# PowerSheet.net
KiCad netlist of a schematic drawn in Altium Designer
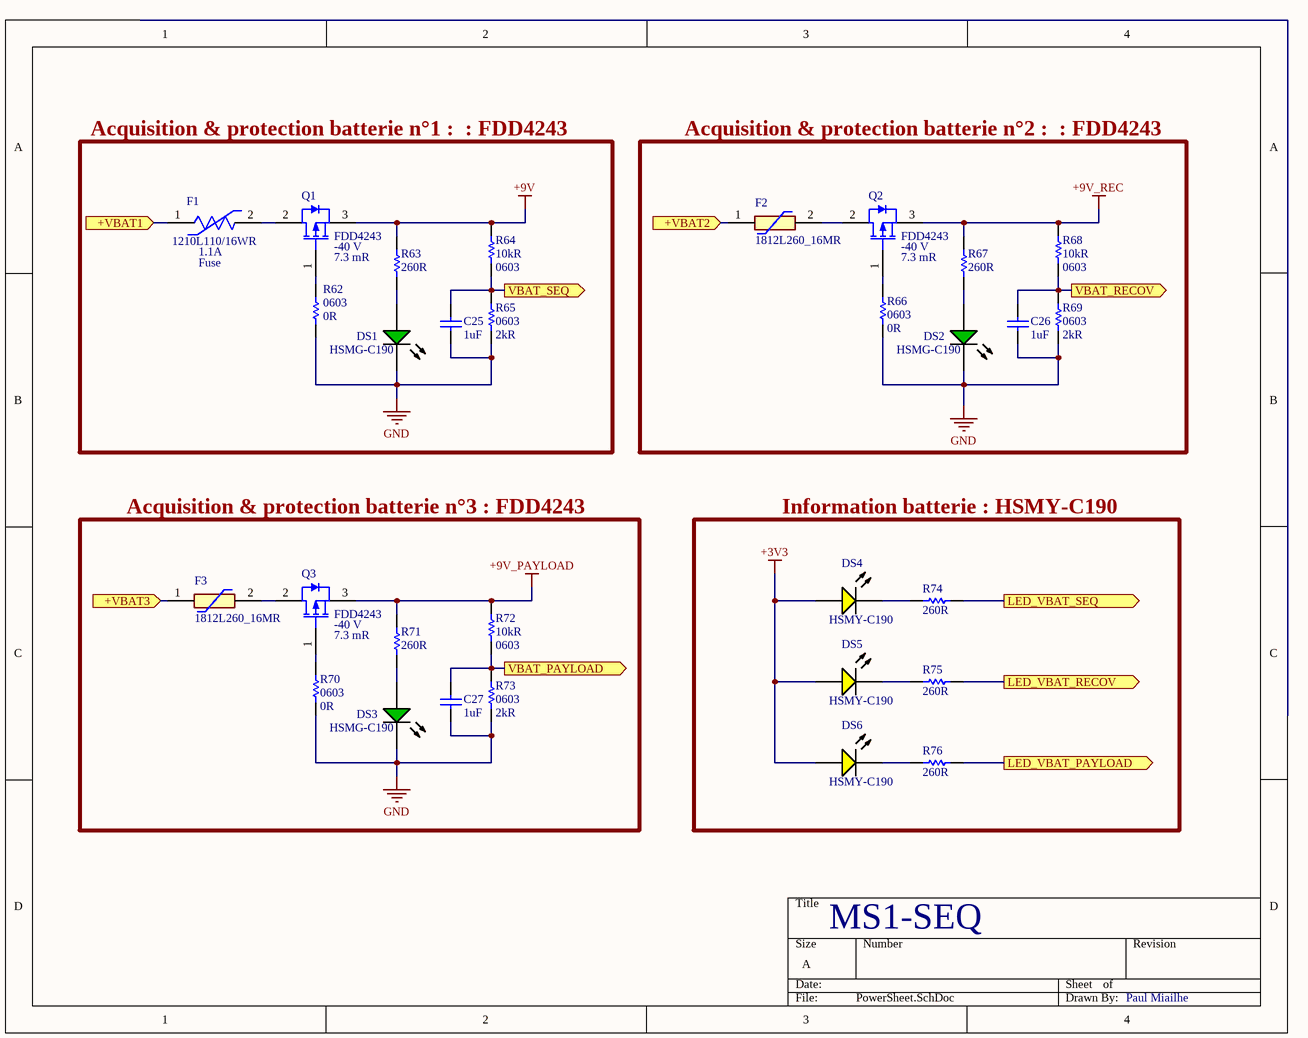
[diagram p0: PowerSheet.SchDoc]

(export (version "E")
  (design (tool "Eeschema 10.0.6"))
  (components
    (comp (ref "C25")
      (value "GRM188R61E105KA12D")
      (footprint "CAPC1608X90X35LL10T15")
      (fields
        (field (name "MANUFACTURER") "Murata")
        (field (name "CAPACITANCE") "1uF")
        (field (name "TOLERANCE") "10%")
        (field (name "VOLTAGE") "25V")
      )
      (libsource (lib "Altium Content Vault") (part "CAP"))
    )
    (comp (ref "C26")
      (value "GRM188R61E105KA12D")
      (footprint "CAPC1608X90X35LL10T15")
      (fields
        (field (name "MANUFACTURER") "Murata")
        (field (name "CAPACITANCE") "1uF")
        (field (name "TOLERANCE") "10%")
        (field (name "VOLTAGE") "25V")
      )
      (libsource (lib "Altium Content Vault") (part "CAP"))
    )
    (comp (ref "C27")
      (value "GRM188R61E105KA12D")
      (footprint "CAPC1608X90X35LL10T15")
      (fields
        (field (name "MANUFACTURER") "Murata")
        (field (name "CAPACITANCE") "1uF")
        (field (name "TOLERANCE") "10%")
        (field (name "VOLTAGE") "25V")
      )
      (libsource (lib "Altium Content Vault") (part "CAP"))
    )
    (comp (ref "DS1")
      (value "HSMG-C190")
      (footprint "AVAG-HSMX-C190_V")
      (description "Chip LED, Green, 2.2 V, -40 to 85 degC, 2-Pin SMD, RoHS, Tape and Reel")
      (libsource (lib "Altium Content Vault") (part "LED-GREEN-AK-2"))
    )
    (comp (ref "DS2")
      (value "HSMG-C190")
      (footprint "AVAG-HSMX-C190_V")
      (description "Chip LED, Green, 2.2 V, -40 to 85 degC, 2-Pin SMD, RoHS, Tape and Reel")
      (libsource (lib "Altium Content Vault") (part "LED-GREEN-AK-2"))
    )
    (comp (ref "DS3")
      (value "HSMG-C190")
      (footprint "AVAG-HSMX-C190_V")
      (description "Chip LED, Green, 2.2 V, -40 to 85 degC, 2-Pin SMD, RoHS, Tape and Reel")
      (libsource (lib "Altium Content Vault") (part "LED-GREEN-AK-2"))
    )
    (comp (ref "DS4")
      (value "HSMY-C190")
      (footprint "AVAG-HSMX-C190_V")
      (description "LED Uni-Color Yellow, 65 mW, 20 mA, -40 to 85 degC, 2-Pin SMD, RoHS, Tape and Reel")
      (fields (field (name "TOLERANCE") "1%"))
      (libsource (lib "Altium Content Vault") (part "LED-YELLOW-AK-2"))
    )
    (comp (ref "DS5")
      (value "HSMY-C190")
      (footprint "AVAG-HSMX-C190_V")
      (description "LED Uni-Color Yellow, 65 mW, 20 mA, -40 to 85 degC, 2-Pin SMD, RoHS, Tape and Reel")
      (fields (field (name "TOLERANCE") "1%"))
      (libsource (lib "Altium Content Vault") (part "LED-YELLOW-AK-2"))
    )
    (comp (ref "DS6")
      (value "HSMY-C190")
      (footprint "AVAG-HSMX-C190_V")
      (description "LED Uni-Color Yellow, 65 mW, 20 mA, -40 to 85 degC, 2-Pin SMD, RoHS, Tape and Reel")
      (fields (field (name "TOLERANCE") "1%"))
      (libsource (lib "Altium Content Vault") (part "LED-YELLOW-AK-2"))
    )
    (comp (ref "F1")
      (value "1210L110/16WR")
      (footprint "FP-1210L110-16WR-MFG")
      (description "PTC RESET FUSE 16V 1.1A 1210")
      (fields
        (field (name "HOLD CURRENT") "1.1A")
        (field (name "CATEGORY") "Fuse")
        (field (name "OCTOPART") "https://octopart.com/1210l110%2F16wr-littelfuse-28867107")
        (field (name "MANUFACTURER") "Littelfuse Inc")
      )
      (libsource (lib "Altium Content Vault") (part "1c6d77a0208143737455a0c7eb396be"))
    )
    (comp (ref "F2")
      (value "1812L260_16MR")
      (footprint "SamacSys:1812L010DR")
      (description "Resettable Fuse")
      (fields
        (field (name "MANUFACTURER_PART_NUMBER") "1812L260/16MR")
        (field (name "MOUSER PART NUMBER") "576-1812L260/16MR")
      )
      (libsource (lib "*") (part "1812L260_16MR"))
    )
    (comp (ref "F3")
      (value "1812L260_16MR")
      (footprint "SamacSys:1812L010DR")
      (description "Resettable Fuse")
      (fields
        (field (name "MANUFACTURER_PART_NUMBER") "1812L260/16MR")
        (field (name "MOUSER PART NUMBER") "576-1812L260/16MR")
      )
      (libsource (lib "*") (part "1812L260_16MR"))
    )
    (comp (ref "Q1")
      (value "FDD4243")
      (footprint "INF-PG-TO252-3-313_L")
      (description "OptiMOS-P2 Power-Transistor, -40 V VDS, -85 A ID, PG-TO252-3-313, Reel, Green")
      (fields
        (field (name "PARTNUMBER") "IPD85P04P4-07")
        (field (name "VDS (MAX)") "-40 V")
        (field (name "RDS (ON) (MAX) (@10V)") "7.3 mR")
        (field (name "MANUFACTURER") "Infineon")
      )
      (libsource (lib "Altium Content Vault") (part "INF-MOSFET-P-3"))
    )
    (comp (ref "Q2")
      (value "FDD4243")
      (footprint "INF-PG-TO252-3-313_L")
      (description "OptiMOS-P2 Power-Transistor, -40 V VDS, -85 A ID, PG-TO252-3-313, Reel, Green")
      (fields
        (field (name "PARTNUMBER") "IPD85P04P4-07")
        (field (name "VDS (MAX)") "-40 V")
        (field (name "RDS (ON) (MAX) (@10V)") "7.3 mR")
        (field (name "MANUFACTURER") "Infineon")
      )
      (libsource (lib "Altium Content Vault") (part "INF-MOSFET-P-3"))
    )
    (comp (ref "Q3")
      (value "FDD4243")
      (footprint "INF-PG-TO252-3-313_L")
      (description "OptiMOS-P2 Power-Transistor, -40 V VDS, -85 A ID, PG-TO252-3-313, Reel, Green")
      (fields
        (field (name "PARTNUMBER") "IPD85P04P4-07")
        (field (name "VDS (MAX)") "-40 V")
        (field (name "RDS (ON) (MAX) (@10V)") "7.3 mR")
        (field (name "MANUFACTURER") "Infineon")
      )
      (libsource (lib "Altium Content Vault") (part "INF-MOSFET-P-3"))
    )
    (comp (ref "R62")
      (value "RC0603JR-070RL")
      (footprint "RESC1608X55X25ML10T15")
      (description "Chip Resistor, 0 Ohm, +/- 5%, 0.1 W, -55 to 155 degC, 0603 (1608 Metric), RoHS, Tape and Reel")
      (fields
        (field (name "TOLERANCE") "5%")
        (field (name "PACKAGE REFERENCE") "0603")
        (field (name "RESISTANCE") "0R")
        (field (name "MANUFACTURER") "Yageo")
      )
      (libsource (lib "Altium Content Vault") (part "RES-2"))
    )
    (comp (ref "R63")
      (value "260R")
      (footprint "RESC1609X50X30NL8T20")
      (fields (field (name "MANUFACTURER") "Vishay Semiconductor"))
      (libsource (lib "Altium Content Vault") (part "RES-2"))
    )
    (comp (ref "R64")
      (value "ERJ3EKF1002V")
      (footprint "RESC1609X55X30LL15T15")
      (description "Chip Resistor, 10 KOhm, +/- 1%, 0.1 W, -55 to 155 degC, 0603 (1608 Metric), RoHS, Tape and Reel")
      (fields
        (field (name "RESISTANCE") "10kR")
        (field (name "CASE CODE (IMPERIAL)") "0603")
        (field (name "TOLERANCE") "1%")
        (field (name "MANUFACTURER") "Panasonic")
      )
      (libsource (lib "Altium Content Vault") (part "RES-2"))
    )
    (comp (ref "R65")
      (value "ERJ-3EKF2001V")
      (footprint "RESC1608X55X30ML15T15")
      (fields
        (field (name "MANUFACTURER") "Panasonic")
        (field (name "CASE CODE (IMPERIAL)") "0603")
        (field (name "RESISTANCE") "2kR")
        (field (name "TOLERANCE") "1%")
      )
      (libsource (lib "Altium Content Vault") (part "RES"))
    )
    (comp (ref "R66")
      (value "RC0603JR-070RL")
      (footprint "RESC1608X55X25ML10T15")
      (description "Chip Resistor, 0 Ohm, +/- 5%, 0.1 W, -55 to 155 degC, 0603 (1608 Metric), RoHS, Tape and Reel")
      (fields
        (field (name "TOLERANCE") "5%")
        (field (name "CASE CODE (IMPERIAL)") "0603")
        (field (name "RESISTANCE") "0R")
        (field (name "MANUFACTURER") "Yageo")
      )
      (libsource (lib "Altium Content Vault") (part "RES-2"))
    )
    (comp (ref "R67")
      (value "260R")
      (footprint "RESC1609X50X30NL8T20")
      (fields (field (name "MANUFACTURER") "Vishay Semiconductor"))
      (libsource (lib "Altium Content Vault") (part "RES-2"))
    )
    (comp (ref "R68")
      (value "ERJ3EKF1002V")
      (footprint "RESC1609X55X30LL15T15")
      (description "Chip Resistor, 10 KOhm, +/- 1%, 0.1 W, -55 to 155 degC, 0603 (1608 Metric), RoHS, Tape and Reel")
      (fields
        (field (name "RESISTANCE") "10kR")
        (field (name "CASE CODE (IMPERIAL)") "0603")
        (field (name "TOLERANCE") "1%")
        (field (name "MANUFACTURER") "Panasonic")
      )
      (libsource (lib "Altium Content Vault") (part "RES-2"))
    )
    (comp (ref "R69")
      (value "ERJ-3EKF2001V")
      (footprint "RESC1608X55X30ML15T15")
      (fields
        (field (name "MANUFACTURER") "Panasonic")
        (field (name "CASE CODE (IMPERIAL)") "0603")
        (field (name "RESISTANCE") "2kR")
        (field (name "TOLERANCE") "1%")
      )
      (libsource (lib "Altium Content Vault") (part "RES"))
    )
    (comp (ref "R70")
      (value "RC0603JR-070RL")
      (footprint "RESC1608X55X25ML10T15")
      (description "Chip Resistor, 0 Ohm, +/- 5%, 0.1 W, -55 to 155 degC, 0603 (1608 Metric), RoHS, Tape and Reel")
      (fields
        (field (name "TOLERANCE") "5%")
        (field (name "CASE CODE (IMPERIAL)") "0603")
        (field (name "RESISTANCE") "0R")
        (field (name "MANUFACTURER") "Yageo")
      )
      (libsource (lib "Altium Content Vault") (part "RES-2"))
    )
    (comp (ref "R71")
      (value "260R")
      (footprint "RESC1609X50X30NL8T20")
      (fields (field (name "MANUFACTURER") "Vishay Semiconductor"))
      (libsource (lib "Altium Content Vault") (part "RES-2"))
    )
    (comp (ref "R72")
      (value "ERJ3EKF1002V")
      (footprint "RESC1609X55X30LL15T15")
      (description "Chip Resistor, 10 KOhm, +/- 1%, 0.1 W, -55 to 155 degC, 0603 (1608 Metric), RoHS, Tape and Reel")
      (fields
        (field (name "RESISTANCE") "10kR")
        (field (name "CASE CODE (IMPERIAL)") "0603")
        (field (name "TOLERANCE") "1%")
        (field (name "MANUFACTURER") "Panasonic")
      )
      (libsource (lib "Altium Content Vault") (part "RES-2"))
    )
    (comp (ref "R73")
      (value "ERJ-3EKF2001V")
      (footprint "RESC1608X55X30ML15T15")
      (fields
        (field (name "MANUFACTURER") "Panasonic")
        (field (name "CASE CODE (IMPERIAL)") "0603")
        (field (name "RESISTANCE") "2kR")
        (field (name "TOLERANCE") "1%")
      )
      (libsource (lib "Altium Content Vault") (part "RES"))
    )
    (comp (ref "R74")
      (value "260R")
      (footprint "RESC1609X50X30NL8T20")
      (fields (field (name "MANUFACTURER") "Vishay Semiconductor"))
      (libsource (lib "Altium Content Vault") (part "RES-2"))
    )
    (comp (ref "R75")
      (value "260R")
      (footprint "RESC1609X50X30NL8T20")
      (fields (field (name "MANUFACTURER") "Vishay Semiconductor"))
      (libsource (lib "Altium Content Vault") (part "RES-2"))
    )
    (comp (ref "R76")
      (value "260R")
      (footprint "RESC1609X50X30NL8T20")
      (fields (field (name "MANUFACTURER") "Vishay Semiconductor"))
      (libsource (lib "Altium Content Vault") (part "RES-2"))
    )
  )
  (nets
    (net (code "1") (name "+3V3") (class "Default")
      (node (ref "DS4") (pin "1") (pinfunction "A_1") (pintype "passive"))
      (node (ref "DS5") (pin "1") (pinfunction "A_1") (pintype "passive"))
      (node (ref "DS6") (pin "1") (pinfunction "A_1") (pintype "passive"))
    )
    (net (code "2") (name "+9V") (class "Default")
      (node (ref "Q1") (pin "3") (pinfunction "SOURCE_3") (pintype "passive"))
      (node (ref "R63") (pin "1") (pinfunction "1_1") (pintype "passive"))
      (node (ref "R64") (pin "2") (pinfunction "2_2") (pintype "passive"))
    )
    (net (code "3") (name "+9V_PAYLOAD") (class "Default")
      (node (ref "Q3") (pin "3") (pinfunction "SOURCE_3") (pintype "passive"))
      (node (ref "R71") (pin "1") (pinfunction "1_1") (pintype "passive"))
      (node (ref "R72") (pin "2") (pinfunction "2_2") (pintype "passive"))
    )
    (net (code "4") (name "+9V_REC") (class "Default")
      (node (ref "Q2") (pin "3") (pinfunction "SOURCE_3") (pintype "passive"))
      (node (ref "R67") (pin "1") (pinfunction "1_1") (pintype "passive"))
      (node (ref "R68") (pin "2") (pinfunction "2_2") (pintype "passive"))
    )
    (net (code "5") (name "/+VBAT1") (class "Default")
      (node (ref "F1") (pin "1") (pinfunction "1_1") (pintype "passive"))
    )
    (net (code "6") (name "/+VBAT2") (class "Default")
      (node (ref "F2") (pin "1") (pinfunction "1_1") (pintype "passive"))
    )
    (net (code "7") (name "/+VBAT3") (class "Default")
      (node (ref "F3") (pin "1") (pinfunction "1_1") (pintype "passive"))
    )
    (net (code "8") (name "/LED_VBAT_PAYLOAD") (class "Default")
      (node (ref "R76") (pin "2") (pinfunction "2_2") (pintype "passive"))
    )
    (net (code "9") (name "/LED_VBAT_RECOV") (class "Default")
      (node (ref "R75") (pin "2") (pinfunction "2_2") (pintype "passive"))
    )
    (net (code "10") (name "/LED_VBAT_SEQ") (class "Default")
      (node (ref "R74") (pin "2") (pinfunction "2_2") (pintype "passive"))
    )
    (net (code "11") (name "/VBAT_PAYLOAD") (class "Default")
      (node (ref "C27") (pin "2") (pinfunction "2_2") (pintype "passive"))
      (node (ref "R72") (pin "1") (pinfunction "1_1") (pintype "passive"))
      (node (ref "R73") (pin "2") (pinfunction "2_2") (pintype "passive"))
    )
    (net (code "12") (name "/VBAT_RECOV") (class "Default")
      (node (ref "C26") (pin "2") (pinfunction "2_2") (pintype "passive"))
      (node (ref "R68") (pin "1") (pinfunction "1_1") (pintype "passive"))
      (node (ref "R69") (pin "2") (pinfunction "2_2") (pintype "passive"))
    )
    (net (code "13") (name "/VBAT_SEQ") (class "Default")
      (node (ref "C25") (pin "2") (pinfunction "2_2") (pintype "passive"))
      (node (ref "R64") (pin "1") (pinfunction "1_1") (pintype "passive"))
      (node (ref "R65") (pin "2") (pinfunction "2_2") (pintype "passive"))
    )
    (net (code "14") (name "GND") (class "Default")
      (node (ref "C25") (pin "1") (pinfunction "1_1") (pintype "passive"))
      (node (ref "C26") (pin "1") (pinfunction "1_1") (pintype "passive"))
      (node (ref "C27") (pin "1") (pinfunction "1_1") (pintype "passive"))
      (node (ref "DS1") (pin "2") (pinfunction "K_2") (pintype "passive"))
      (node (ref "DS2") (pin "2") (pinfunction "K_2") (pintype "passive"))
      (node (ref "DS3") (pin "2") (pinfunction "K_2") (pintype "passive"))
      (node (ref "R62") (pin "1") (pinfunction "1_1") (pintype "passive"))
      (node (ref "R65") (pin "1") (pinfunction "1_1") (pintype "passive"))
      (node (ref "R66") (pin "1") (pinfunction "1_1") (pintype "passive"))
      (node (ref "R69") (pin "1") (pinfunction "1_1") (pintype "passive"))
      (node (ref "R70") (pin "1") (pinfunction "1_1") (pintype "passive"))
      (node (ref "R73") (pin "1") (pinfunction "1_1") (pintype "passive"))
    )
    (net (code "15") (name "Net-(DS1-A)") (class "Default")
      (node (ref "DS1") (pin "1") (pinfunction "A_1") (pintype "passive"))
      (node (ref "R63") (pin "2") (pinfunction "2_2") (pintype "passive"))
    )
    (net (code "16") (name "Net-(DS2-A)") (class "Default")
      (node (ref "DS2") (pin "1") (pinfunction "A_1") (pintype "passive"))
      (node (ref "R67") (pin "2") (pinfunction "2_2") (pintype "passive"))
    )
    (net (code "17") (name "Net-(DS3-A)") (class "Default")
      (node (ref "DS3") (pin "1") (pinfunction "A_1") (pintype "passive"))
      (node (ref "R71") (pin "2") (pinfunction "2_2") (pintype "passive"))
    )
    (net (code "18") (name "Net-(DS4-K)") (class "Default")
      (node (ref "DS4") (pin "2") (pinfunction "K_2") (pintype "passive"))
      (node (ref "R74") (pin "1") (pinfunction "1_1") (pintype "passive"))
    )
    (net (code "19") (name "Net-(DS5-K)") (class "Default")
      (node (ref "DS5") (pin "2") (pinfunction "K_2") (pintype "passive"))
      (node (ref "R75") (pin "1") (pinfunction "1_1") (pintype "passive"))
    )
    (net (code "20") (name "Net-(DS6-K)") (class "Default")
      (node (ref "DS6") (pin "2") (pinfunction "K_2") (pintype "passive"))
      (node (ref "R76") (pin "1") (pinfunction "1_1") (pintype "passive"))
    )
    (net (code "21") (name "Net-(Q1-DRAIN)") (class "Default")
      (node (ref "F1") (pin "2") (pinfunction "2_2") (pintype "passive"))
      (node (ref "Q1") (pin "2") (pinfunction "DRAIN_2") (pintype "passive"))
    )
    (net (code "22") (name "Net-(Q1-GATE)") (class "Default")
      (node (ref "Q1") (pin "1") (pinfunction "GATE_1") (pintype "passive"))
      (node (ref "R62") (pin "2") (pinfunction "2_2") (pintype "passive"))
    )
    (net (code "23") (name "Net-(Q2-DRAIN)") (class "Default")
      (node (ref "F2") (pin "2") (pinfunction "2_2") (pintype "passive"))
      (node (ref "Q2") (pin "2") (pinfunction "DRAIN_2") (pintype "passive"))
    )
    (net (code "24") (name "Net-(Q2-GATE)") (class "Default")
      (node (ref "Q2") (pin "1") (pinfunction "GATE_1") (pintype "passive"))
      (node (ref "R66") (pin "2") (pinfunction "2_2") (pintype "passive"))
    )
    (net (code "25") (name "Net-(Q3-DRAIN)") (class "Default")
      (node (ref "F3") (pin "2") (pinfunction "2_2") (pintype "passive"))
      (node (ref "Q3") (pin "2") (pinfunction "DRAIN_2") (pintype "passive"))
    )
    (net (code "26") (name "Net-(Q3-GATE)") (class "Default")
      (node (ref "Q3") (pin "1") (pinfunction "GATE_1") (pintype "passive"))
      (node (ref "R70") (pin "2") (pinfunction "2_2") (pintype "passive"))
    )
  )
)
